# eps_bt.net
KiCad netlist of a schematic drawn in Altium Designer
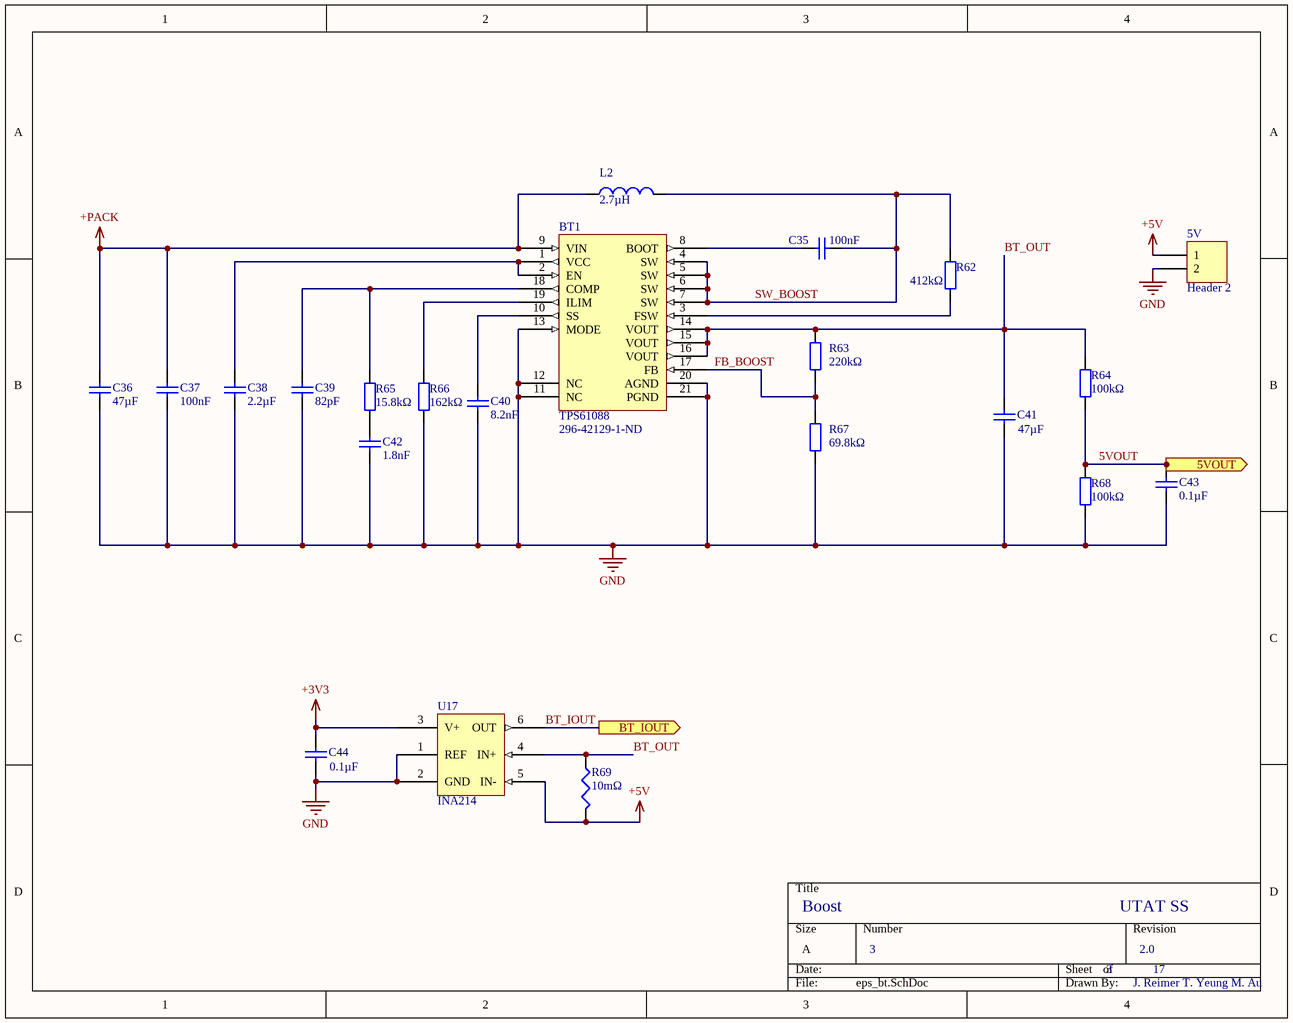
[diagram p0: eps_bt.SchDoc]

(export (version "E")
  (design (tool "Eeschema 10.0.6"))
  (components
    (comp (ref "5V")
      (value "Header 2")
      (footprint "CON2_SCREW_5.00MM_691102710002")
      (description "Battery Header, 2-Pin")
      (fields (field (name "PUBLISHER") "Altium Limited"))
      (libsource (lib "Miscellaneous Connectors") (part "Header 2"))
    )
    (comp (ref "BT1")
      (value "TPS61088")
      (footprint "QFN50P450X350X100-21N")
      (description "Boost converter")
      (fields (field (name "SUPPLIER PART NUMBER 1") "296-42129-1-ND"))
      (libsource (lib "EPS") (part "TPS61088"))
    )
    (comp (ref "C35")
      (value "100nF")
      (footprint "1608[0603]")
      (description "Capacitor, Cbst")
      (fields (field (name "PUBLISHER") "Altium Limited"))
      (libsource (lib "Miscellaneous Devices") (part "Cap"))
    )
    (comp (ref "C36")
      (value "47µF")
      (footprint "C0805")
      (description "Capacitor, Cinbt1")
      (fields (field (name "PUBLISHER") "Altium Limited"))
      (libsource (lib "Miscellaneous Devices") (part "Cap"))
    )
    (comp (ref "C37")
      (value "100nF")
      (footprint "C0805")
      (description "Capacitor, Cinbt2")
      (fields (field (name "PUBLISHER") "Altium Limited"))
      (libsource (lib "Miscellaneous Devices") (part "Cap"))
    )
    (comp (ref "C38")
      (value "2.2µF")
      (footprint "1608[0603]")
      (description "Capacitor, Cvcc1")
      (fields (field (name "PUBLISHER") "Altium Limited"))
      (libsource (lib "Miscellaneous Devices") (part "Cap"))
    )
    (comp (ref "C39")
      (value "82pF")
      (footprint "1608[0603]")
      (description "Capacitor, Ccomp1")
      (fields (field (name "PUBLISHER") "Altium Limited"))
      (libsource (lib "Miscellaneous Devices") (part "Cap"))
    )
    (comp (ref "C40")
      (value "8.2nF")
      (footprint "1608[0603]")
      (description "Capacitor, Css1")
      (fields (field (name "PUBLISHER") "Altium Limited"))
      (libsource (lib "Miscellaneous Devices") (part "Cap"))
    )
    (comp (ref "C41")
      (value "47µF")
      (footprint "C0805")
      (description "Capacitor, Cout")
      (fields (field (name "PUBLISHER") "Altium Limited"))
      (libsource (lib "Miscellaneous Devices") (part "Cap"))
    )
    (comp (ref "C42")
      (value "1.8nF")
      (footprint "1608[0603]")
      (description "Capacitor, Ccomp2")
      (fields (field (name "PUBLISHER") "Altium Limited"))
      (libsource (lib "Miscellaneous Devices") (part "Cap"))
    )
    (comp (ref "C43")
      (value "0.1µF")
      (footprint "1608[0603]")
      (description "Capacitor")
      (fields (field (name "PUBLISHER") "Altium Limited"))
      (libsource (lib "Miscellaneous Devices") (part "Cap"))
    )
    (comp (ref "C44")
      (value "0.1µF")
      (footprint "1608[0603]")
      (description "Capacitor (Semiconductor SIM Model)")
      (fields (field (name "PUBLISHER") "Altium Limited"))
      (libsource (lib "Miscellaneous Devices") (part "Cap Semi"))
    )
    (comp (ref "L2")
      (value "2.7µH")
      (footprint "74439358022")
      (description "Inductor, Lbt")
      (fields (field (name "PUBLISHER") "Altium Limited"))
      (libsource (lib "Miscellaneous Devices") (part "Inductor"))
    )
    (comp (ref "R62")
      (value "412kΩ")
      (footprint "1608[0603]")
      (description "Resistor, Rt")
      (fields (field (name "PUBLISHER") "Altium Limited"))
      (libsource (lib "") (part "Res2_1"))
    )
    (comp (ref "R63")
      (value "220kΩ")
      (footprint "1608[0603]")
      (description "Resistor, Rfbt_bt1")
      (fields (field (name "PUBLISHER") "Altium Limited"))
      (libsource (lib "Miscellaneous Devices") (part "Res2"))
    )
    (comp (ref "R64")
      (value "100kΩ")
      (footprint "1608[0603]")
      (description "Resistor")
      (fields (field (name "PUBLISHER") "Altium Limited"))
      (libsource (lib "Miscellaneous Devices") (part "Res2"))
    )
    (comp (ref "R65")
      (value "15.8kΩ")
      (footprint "1608[0603]")
      (description "Resistor, Rcomp1")
      (fields (field (name "PUBLISHER") "Altium Limited"))
      (libsource (lib "Miscellaneous Devices") (part "Res2"))
    )
    (comp (ref "R66")
      (value "162kΩ")
      (footprint "1608[0603]")
      (description "Resistor, Rlim1")
      (fields (field (name "PUBLISHER") "Altium Limited"))
      (libsource (lib "Miscellaneous Devices") (part "Res2"))
    )
    (comp (ref "R67")
      (value "69.8kΩ")
      (footprint "1608[0603]")
      (description "Resistor, Rfbb_bt1")
      (fields (field (name "PUBLISHER") "Altium Limited"))
      (libsource (lib "Miscellaneous Devices") (part "Res2"))
    )
    (comp (ref "R68")
      (value "100kΩ")
      (footprint "1608[0603]")
      (description "Resistor")
      (fields (field (name "PUBLISHER") "Altium Limited"))
      (libsource (lib "Miscellaneous Devices") (part "Res2"))
    )
    (comp (ref "R69")
      (value "10mΩ")
      (footprint "C1206")
      (description "Resistor")
      (fields (field (name "PUBLISHER") "Altium Limited"))
      (libsource (lib "Miscellaneous Devices") (part "Res3"))
    )
    (comp (ref "U17")
      (value "INA214")
      (footprint "SOT65P210X110-6N")
      (description "Current monitor")
      (libsource (lib "heron-general") (part "INA214"))
    )
  )
  (nets
    (net (code "1") (name "+3V3") (class "Default")
      (node (ref "C44") (pin "1") (pinfunction "1_1") (pintype "passive"))
      (node (ref "U17") (pin "3") (pinfunction "V+_3") (pintype "power_in"))
    )
    (net (code "2") (name "+5V") (class "Default")
      (node (ref "5V") (pin "1") (pinfunction "1_1") (pintype "passive"))
      (node (ref "R69") (pin "2") (pinfunction "2_2") (pintype "passive"))
      (node (ref "U17") (pin "5") (pinfunction "IN-_5") (pintype "input"))
    )
    (net (code "3") (name "+PACK") (class "Default")
      (node (ref "BT1") (pin "9") (pinfunction "VIN_9") (pintype "input"))
      (node (ref "C36") (pin "2") (pinfunction "2_2") (pintype "passive"))
      (node (ref "C37") (pin "2") (pinfunction "2_2") (pintype "passive"))
      (node (ref "L2") (pin "1") (pinfunction "1_1") (pintype "passive"))
    )
    (net (code "4") (name "/5VOUT") (class "Default")
      (node (ref "C43") (pin "1") (pinfunction "1_1") (pintype "passive"))
      (node (ref "R64") (pin "1") (pinfunction "1_1") (pintype "passive"))
      (node (ref "R68") (pin "2") (pinfunction "2_2") (pintype "passive"))
    )
    (net (code "5") (name "/BT_IOUT") (class "Default")
      (node (ref "U17") (pin "6") (pinfunction "OUT_6") (pintype "output"))
    )
    (net (code "6") (name "/BT_OUT") (class "Default")
      (node (ref "BT1") (pin "14") (pinfunction "VOUT_14") (pintype "output"))
      (node (ref "BT1") (pin "15") (pinfunction "VOUT_15") (pintype "output"))
      (node (ref "BT1") (pin "16") (pinfunction "VOUT_16") (pintype "output"))
      (node (ref "C41") (pin "2") (pinfunction "2_2") (pintype "passive"))
      (node (ref "R63") (pin "2") (pinfunction "2_2") (pintype "passive"))
      (node (ref "R64") (pin "2") (pinfunction "2_2") (pintype "passive"))
      (node (ref "R69") (pin "1") (pinfunction "1_1") (pintype "passive"))
      (node (ref "U17") (pin "4") (pinfunction "IN+_4") (pintype "input"))
    )
    (net (code "7") (name "/FB_BOOST") (class "Default")
      (node (ref "BT1") (pin "17") (pinfunction "FB_17") (pintype "input"))
      (node (ref "R63") (pin "1") (pinfunction "1_1") (pintype "passive"))
      (node (ref "R67") (pin "2") (pinfunction "2_2") (pintype "passive"))
    )
    (net (code "8") (name "/SW_BOOST") (class "Default")
      (node (ref "BT1") (pin "4") (pinfunction "SW_4") (pintype "input"))
      (node (ref "BT1") (pin "5") (pinfunction "SW_5") (pintype "input"))
      (node (ref "BT1") (pin "6") (pinfunction "SW_6") (pintype "input"))
      (node (ref "BT1") (pin "7") (pinfunction "SW_7") (pintype "input"))
      (node (ref "C35") (pin "1") (pinfunction "1_1") (pintype "passive"))
      (node (ref "L2") (pin "2") (pinfunction "2_2") (pintype "passive"))
      (node (ref "R62") (pin "1") (pinfunction "1_1") (pintype "passive"))
    )
    (net (code "9") (name "GND") (class "Default")
      (node (ref "5V") (pin "2") (pinfunction "2_2") (pintype "passive"))
      (node (ref "BT1") (pin "11") (pinfunction "NC_11") (pintype "passive"))
      (node (ref "BT1") (pin "12") (pinfunction "NC_12") (pintype "passive"))
      (node (ref "BT1") (pin "13") (pinfunction "MODE_13") (pintype "input"))
      (node (ref "BT1") (pin "20") (pinfunction "AGND_20") (pintype "power_in"))
      (node (ref "BT1") (pin "21") (pinfunction "PGND_21") (pintype "power_in"))
      (node (ref "C36") (pin "1") (pinfunction "1_1") (pintype "passive"))
      (node (ref "C37") (pin "1") (pinfunction "1_1") (pintype "passive"))
      (node (ref "C38") (pin "1") (pinfunction "1_1") (pintype "passive"))
      (node (ref "C39") (pin "1") (pinfunction "1_1") (pintype "passive"))
      (node (ref "C40") (pin "1") (pinfunction "1_1") (pintype "passive"))
      (node (ref "C41") (pin "1") (pinfunction "1_1") (pintype "passive"))
      (node (ref "C42") (pin "1") (pinfunction "1_1") (pintype "passive"))
      (node (ref "C43") (pin "2") (pinfunction "2_2") (pintype "passive"))
      (node (ref "C44") (pin "2") (pinfunction "2_2") (pintype "passive"))
      (node (ref "R66") (pin "1") (pinfunction "1_1") (pintype "passive"))
      (node (ref "R67") (pin "1") (pinfunction "1_1") (pintype "passive"))
      (node (ref "R68") (pin "1") (pinfunction "1_1") (pintype "passive"))
      (node (ref "U17") (pin "1") (pinfunction "REF_1") (pintype "passive"))
      (node (ref "U17") (pin "2") (pinfunction "GND_2") (pintype "power_in"))
    )
    (net (code "10") (name "Net-(BT1-BOOT)") (class "Default")
      (node (ref "BT1") (pin "8") (pinfunction "BOOT_8") (pintype "output"))
      (node (ref "C35") (pin "2") (pinfunction "2_2") (pintype "passive"))
    )
    (net (code "11") (name "Net-(BT1-COMP)") (class "Default")
      (node (ref "BT1") (pin "18") (pinfunction "COMP_18") (pintype "output"))
      (node (ref "C39") (pin "2") (pinfunction "2_2") (pintype "passive"))
      (node (ref "R65") (pin "2") (pinfunction "2_2") (pintype "passive"))
    )
    (net (code "12") (name "Net-(BT1-EN)") (class "Default")
      (node (ref "BT1") (pin "1") (pinfunction "VCC_1") (pintype "output"))
      (node (ref "BT1") (pin "2") (pinfunction "EN_2") (pintype "input"))
      (node (ref "C38") (pin "2") (pinfunction "2_2") (pintype "passive"))
    )
    (net (code "13") (name "Net-(BT1-FSW)") (class "Default")
      (node (ref "BT1") (pin "3") (pinfunction "FSW_3") (pintype "input"))
      (node (ref "R62") (pin "2") (pinfunction "2_2") (pintype "passive"))
    )
    (net (code "14") (name "Net-(BT1-ILIM)") (class "Default")
      (node (ref "BT1") (pin "19") (pinfunction "ILIM_19") (pintype "output"))
      (node (ref "R66") (pin "2") (pinfunction "2_2") (pintype "passive"))
    )
    (net (code "15") (name "Net-(BT1-SS)") (class "Default")
      (node (ref "BT1") (pin "10") (pinfunction "SS_10") (pintype "output"))
      (node (ref "C40") (pin "2") (pinfunction "2_2") (pintype "passive"))
    )
    (net (code "16") (name "Net-(C42-Pad2)") (class "Default")
      (node (ref "C42") (pin "2") (pinfunction "2_2") (pintype "passive"))
      (node (ref "R65") (pin "1") (pinfunction "1_1") (pintype "passive"))
    )
  )
)
